# Arduino_Leonardo-REV3b.net
KiCad netlist of a schematic drawn in EAGLE
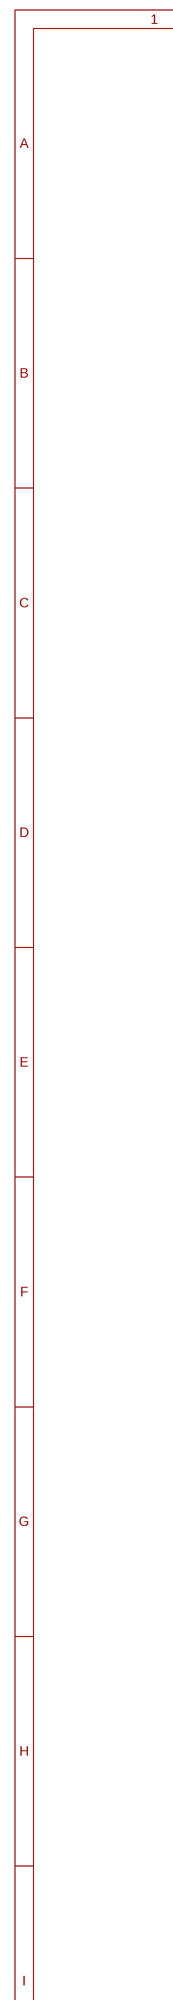
[diagram p0: schematic, sheet 1, part 1 of 2]
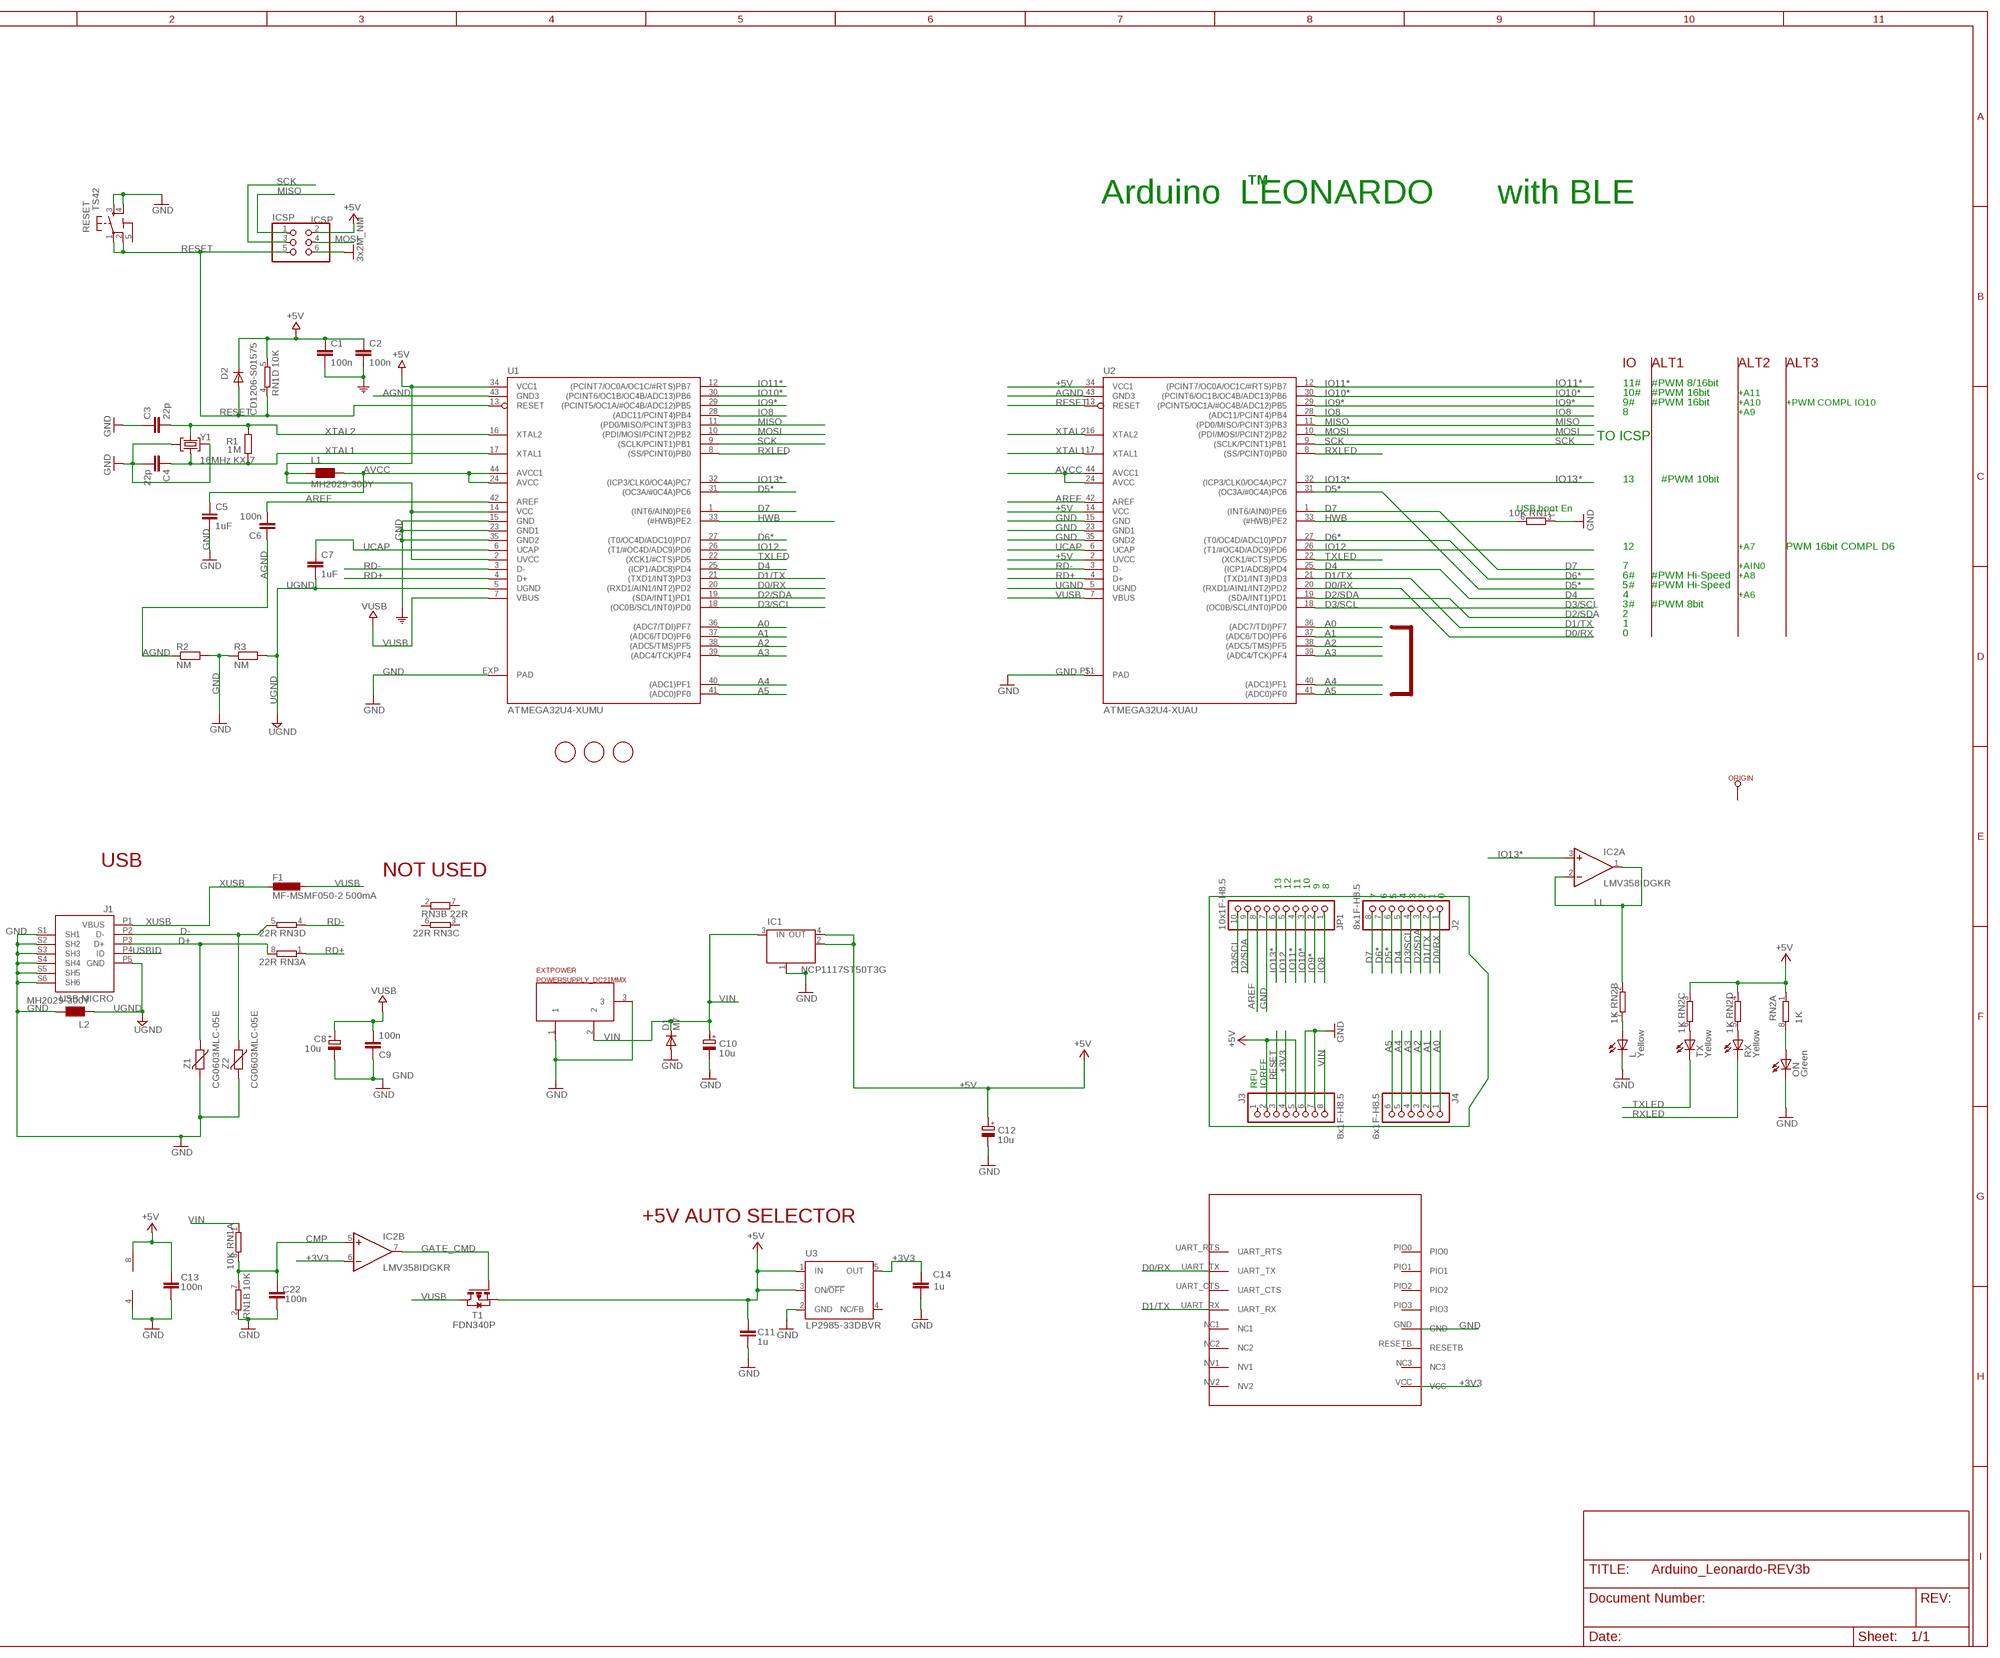
[diagram p1: schematic, sheet 1, part 2 of 2]

(export (version "E")
  (design (tool "Eeschema 10.0.6"))
  (components
    (comp (ref "C1")
      (value "100n")
      (footprint "eagle-import:C0603-ROUND")
      (libsource (lib "eagle-import") (part "C-EUC0603"))
    )
    (comp (ref "C2")
      (value "100n")
      (footprint "eagle-import:C0603-ROUND")
      (libsource (lib "eagle-import") (part "C-EUC0603"))
    )
    (comp (ref "C3")
      (value "22p")
      (footprint "eagle-import:C0603-ROUND")
      (libsource (lib "eagle-import") (part "C-EUC0603"))
    )
    (comp (ref "C4")
      (value "22p")
      (footprint "eagle-import:C0603-ROUND")
      (libsource (lib "eagle-import") (part "C-EUC0603"))
    )
    (comp (ref "C5")
      (value "1uF")
      (footprint "eagle-import:C0603-ROUND")
      (libsource (lib "eagle-import") (part "C-EUC0603"))
    )
    (comp (ref "C6")
      (value "100n")
      (footprint "eagle-import:C0603-ROUND")
      (libsource (lib "eagle-import") (part "C-EUC0603"))
    )
    (comp (ref "C7")
      (value "1uF")
      (footprint "eagle-import:C0603-ROUND")
      (libsource (lib "eagle-import") (part "C-EUC0603"))
    )
    (comp (ref "C8")
      (value "10u")
      (footprint "eagle-import:SMC_B")
      (libsource (lib "eagle-import") (part "CPOL-EUSMCB"))
    )
    (comp (ref "C9")
      (value "100n")
      (footprint "eagle-import:C0603-ROUND")
      (libsource (lib "eagle-import") (part "C-EUC0603"))
    )
    (comp (ref "C10")
      (value "10u")
      (footprint "eagle-import:SMC_B")
      (libsource (lib "eagle-import") (part "CPOL-EUSMCB"))
    )
    (comp (ref "C11")
      (value "1u")
      (footprint "eagle-import:C0603-ROUND")
      (libsource (lib "eagle-import") (part "C-EUC0603"))
    )
    (comp (ref "C12")
      (value "10u")
      (footprint "eagle-import:SMC_B")
      (libsource (lib "eagle-import") (part "CPOL-EUSMCB"))
    )
    (comp (ref "C13")
      (value "100n")
      (footprint "eagle-import:C0603-ROUND")
      (libsource (lib "eagle-import") (part "C-EUC0603"))
    )
    (comp (ref "C14")
      (value "1u")
      (footprint "eagle-import:C0603-ROUND")
      (libsource (lib "eagle-import") (part "C-EUC0603"))
    )
    (comp (ref "C22")
      (value "100n")
      (footprint "eagle-import:C0603-ROUND")
      (libsource (lib "eagle-import") (part "C-EUC0603"))
    )
    (comp (ref "D1")
      (value "M7")
      (footprint "eagle-import:SMB")
      (libsource (lib "eagle-import") (part "DIODE-SMB"))
    )
    (comp (ref "D2")
      (value "CD1206-S01575")
      (footprint "eagle-import:MINIMELF")
      (libsource (lib "eagle-import") (part "DIODE-MINIMELF"))
    )
    (comp (ref "EXTPOWER")
      (value "POWERSUPPLY_DC21MMX")
      (footprint "eagle-import:POWERSUPPLY_DC-21MM")
      (libsource (lib "eagle-import") (part "POWERSUPPLY_DC21MMX"))
    )
    (comp (ref "F1")
      (value "MF-MSMF050-2 500mA")
      (footprint "eagle-import:L1812")
      (libsource (lib "eagle-import") (part "L-EUL1812"))
    )
    (comp (ref "FID1")
      (value "FIDUCIALMOUNT")
      (footprint "eagle-import:FIDUCIA-MOUNT")
      (libsource (lib "eagle-import") (part "FIDUCIALMOUNT"))
    )
    (comp (ref "FID2")
      (value "FIDUCIALMOUNT")
      (footprint "eagle-import:FIDUCIA-MOUNT")
      (libsource (lib "eagle-import") (part "FIDUCIALMOUNT"))
    )
    (comp (ref "FID3")
      (value "FIDUCIALMOUNT")
      (footprint "eagle-import:FIDUCIA-MOUNT")
      (libsource (lib "eagle-import") (part "FIDUCIALMOUNT"))
    )
    (comp (ref "IC1")
      (value "NCP1117ST50T3G")
      (footprint "eagle-import:SOT223")
      (libsource (lib "eagle-import") (part "MC33269ST-3.3T3"))
    )
    (comp (ref "IC2")
      (value "LMV358IDGKR")
      (footprint "eagle-import:MSOP08")
      (libsource (lib "eagle-import") (part "LMV358?MMX"))
    )
    (comp (ref "ICSP")
      (value "ICSP")
      (footprint "eagle-import:2X03")
      (libsource (lib "eagle-import") (part "PINHD-2X3"))
    )
    (comp (ref "J1")
      (value "USB MICRO")
      (footprint "eagle-import:CON2_USB_MICRO_B_AT")
      (libsource (lib "eagle-import") (part "MYCON2_USB-MINI-B"))
    )
    (comp (ref "J2")
      (value "8x1F-H8.5")
      (footprint "eagle-import:1X08")
      (libsource (lib "eagle-import") (part "PINHD-1X8"))
    )
    (comp (ref "J3")
      (value "8x1F-H8.5")
      (footprint "eagle-import:1X08")
      (libsource (lib "eagle-import") (part "PINHD-1X8"))
    )
    (comp (ref "J4")
      (value "6x1F-H8.5")
      (footprint "eagle-import:1X06")
      (libsource (lib "eagle-import") (part "PINHD-1X6"))
    )
    (comp (ref "JP1")
      (value "10x1F-H8.5")
      (footprint "eagle-import:1X10")
      (libsource (lib "eagle-import") (part "PINHD-1X10"))
    )
    (comp (ref "L")
      (value "Yellow")
      (footprint "eagle-import:CHIPLED_0805")
      (libsource (lib "eagle-import") (part "LEDCHIPLED_0805"))
    )
    (comp (ref "L1")
      (value "MH2029-300Y")
      (footprint "eagle-import:0805")
      (libsource (lib "eagle-import") (part "WE-CBF_0805"))
    )
    (comp (ref "L2")
      (value "MH2029-300Y")
      (footprint "eagle-import:0805")
      (libsource (lib "eagle-import") (part "WE-CBF_0805"))
    )
    (comp (ref "ON")
      (value "Green")
      (footprint "eagle-import:CHIPLED_0805")
      (libsource (lib "eagle-import") (part "LEDCHIPLED_0805"))
    )
    (comp (ref "ORIGIN")
      (value "TP_SP")
      (footprint "eagle-import:TP-SP")
      (libsource (lib "eagle-import") (part "TP_SP"))
    )
    (comp (ref "R1")
      (value "1M")
      (footprint "eagle-import:R0603-ROUND")
      (libsource (lib "eagle-import") (part "R-EU_R0603"))
    )
    (comp (ref "R2")
      (value "NM")
      (footprint "eagle-import:R0402")
      (libsource (lib "eagle-import") (part "R-EU_R0402"))
    )
    (comp (ref "R3")
      (value "NM")
      (footprint "eagle-import:R0402")
      (libsource (lib "eagle-import") (part "R-EU_R0402"))
    )
    (comp (ref "RESET")
      (value "TS42")
      (footprint "eagle-import:TS42")
      (libsource (lib "eagle-import") (part "TS42"))
    )
    (comp (ref "RN1")
      (value "10K")
      (footprint "eagle-import:CAY16")
      (libsource (lib "eagle-import") (part "4R-NCAY16"))
    )
    (comp (ref "RN2")
      (value "1K")
      (footprint "eagle-import:CAY16")
      (libsource (lib "eagle-import") (part "4R-NCAY16"))
    )
    (comp (ref "RN3")
      (value "22R")
      (footprint "eagle-import:CAY16")
      (libsource (lib "eagle-import") (part "4R-NCAY16"))
    )
    (comp (ref "RX")
      (value "Yellow")
      (footprint "eagle-import:CHIPLED_0805")
      (libsource (lib "eagle-import") (part "LEDCHIPLED_0805"))
    )
    (comp (ref "T1")
      (value "FDN340P")
      (footprint "eagle-import:SOT-23")
      (libsource (lib "eagle-import") (part "PMOSSOT23"))
    )
    (comp (ref "TX")
      (value "Yellow")
      (footprint "eagle-import:CHIPLED_0805")
      (libsource (lib "eagle-import") (part "LEDCHIPLED_0805"))
    )
    (comp (ref "U$1")
      (value "HM-11")
      (footprint "eagle-import:HM-11")
      (libsource (lib "eagle-import") (part "HM-11"))
    )
    (comp (ref "U1")
      (value "ATMEGA32U4-XUMU")
      (footprint "eagle-import:QFN44ML7X7")
      (libsource (lib "eagle-import") (part "ATMEGA32U4-XUMU"))
    )
    (comp (ref "U2")
      (value "ATMEGA32U4-XUAU")
      (footprint "eagle-import:TQFP44-PAD")
      (libsource (lib "eagle-import") (part "ATMEGA32U4-XUAU"))
    )
    (comp (ref "U3")
      (value "LP2985-33DBVR")
      (footprint "eagle-import:SOT23-DBV")
      (libsource (lib "eagle-import") (part "LP2985-XXDBVR33"))
    )
    (comp (ref "Y1")
      (value "16MHz KX-7")
      (footprint "eagle-import:CRYSTAL-3.2-2.5")
      (libsource (lib "eagle-import") (part "CRYSTAL-3.2-2.5"))
    )
    (comp (ref "Z1")
      (value "CG0603MLC-05E")
      (footprint "eagle-import:CT_CN0603")
      (libsource (lib "eagle-import") (part "VARISTORCN0603"))
    )
    (comp (ref "Z2")
      (value "CG0603MLC-05E")
      (footprint "eagle-import:CT_CN0603")
      (libsource (lib "eagle-import") (part "VARISTORCN0603"))
    )
  )
  (nets
    (net (code "1") (name "+5V") (class "Default")
      (node (ref "C1") (pin "1") (pinfunction "1_1") (pintype "passive"))
      (node (ref "C11") (pin "2") (pinfunction "2_2") (pintype "passive"))
      (node (ref "C12") (pin "+") (pinfunction "+_+") (pintype "passive"))
      (node (ref "C13") (pin "1") (pinfunction "1_1") (pintype "passive"))
      (node (ref "C2") (pin "1") (pinfunction "1_1") (pintype "passive"))
      (node (ref "D2") (pin "C") (pinfunction "C_C") (pintype "passive"))
      (node (ref "IC1") (pin "2") (pinfunction "OUT_2") (pintype "passive"))
      (node (ref "IC1") (pin "4") (pinfunction "OUT_4") (pintype "passive"))
      (node (ref "IC2") (pin "8") (pinfunction "V+_8") (pintype "power_in"))
      (node (ref "ICSP") (pin "2") (pinfunction "2_2") (pintype "passive"))
      (node (ref "J3") (pin "2") (pinfunction "2_2") (pintype "passive"))
      (node (ref "J3") (pin "5") (pinfunction "5_5") (pintype "passive"))
      (node (ref "L1") (pin "1") (pinfunction "1_1") (pintype "passive"))
      (node (ref "RN1") (pin "5") (pinfunction "2_5") (pintype "passive"))
      (node (ref "RN2") (pin "1") (pinfunction "1_1") (pintype "passive"))
      (node (ref "RN2") (pin "3") (pinfunction "1_3") (pintype "passive"))
      (node (ref "RN2") (pin "4") (pinfunction "1_4") (pintype "passive"))
      (node (ref "T1") (pin "2") (pinfunction "S_2") (pintype "passive"))
      (node (ref "U1") (pin "14") (pinfunction "VCC_14") (pintype "power_in"))
      (node (ref "U1") (pin "2") (pinfunction "UVCC_2") (pintype "power_in"))
      (node (ref "U1") (pin "34") (pinfunction "VCC1_34") (pintype "power_in"))
      (node (ref "U2") (pin "14") (pinfunction "VCC_14") (pintype "power_in"))
      (node (ref "U2") (pin "2") (pinfunction "UVCC_2") (pintype "power_in"))
      (node (ref "U2") (pin "34") (pinfunction "VCC1_34") (pintype "power_in"))
      (node (ref "U3") (pin "1") (pinfunction "IN_1") (pintype "input"))
      (node (ref "U3") (pin "3") (pinfunction "ON/~{OFF}_3") (pintype "input"))
    )
    (net (code "2") (name "/+3V3") (class "Default")
      (node (ref "C14") (pin "2") (pinfunction "2_2") (pintype "passive"))
      (node (ref "IC2") (pin "6") (pinfunction "-IN_6") (pintype "input"))
      (node (ref "J3") (pin "4") (pinfunction "4_4") (pintype "passive"))
      (node (ref "U3") (pin "5") (pinfunction "OUT_5") (pintype "passive"))
    )
    (net (code "3") (name "/5-GND") (class "Default")
      (node (ref "RESET") (pin "5") (pinfunction "5-GND_5") (pintype "power_in"))
    )
    (net (code "4") (name "/A0") (class "Default")
      (node (ref "J4") (pin "1") (pinfunction "1_1") (pintype "passive"))
      (node (ref "U1") (pin "36") (pinfunction "(ADC7/TDI)PF7_36") (pintype "bidirectional"))
      (node (ref "U2") (pin "36") (pinfunction "(ADC7/TDI)PF7_36") (pintype "bidirectional"))
    )
    (net (code "5") (name "/A1") (class "Default")
      (node (ref "J4") (pin "2") (pinfunction "2_2") (pintype "passive"))
      (node (ref "U1") (pin "37") (pinfunction "(ADC6/TDO)PF6_37") (pintype "bidirectional"))
      (node (ref "U2") (pin "37") (pinfunction "(ADC6/TDO)PF6_37") (pintype "bidirectional"))
    )
    (net (code "6") (name "/A2") (class "Default")
      (node (ref "J4") (pin "3") (pinfunction "3_3") (pintype "passive"))
      (node (ref "U1") (pin "38") (pinfunction "(ADC5/TMS)PF5_38") (pintype "bidirectional"))
      (node (ref "U2") (pin "38") (pinfunction "(ADC5/TMS)PF5_38") (pintype "bidirectional"))
    )
    (net (code "7") (name "/A3") (class "Default")
      (node (ref "J4") (pin "4") (pinfunction "4_4") (pintype "passive"))
      (node (ref "U1") (pin "39") (pinfunction "(ADC4/TCK)PF4_39") (pintype "bidirectional"))
      (node (ref "U2") (pin "39") (pinfunction "(ADC4/TCK)PF4_39") (pintype "bidirectional"))
    )
    (net (code "8") (name "/A4") (class "Default")
      (node (ref "J4") (pin "5") (pinfunction "5_5") (pintype "passive"))
      (node (ref "U1") (pin "40") (pinfunction "(ADC1)PF1_40") (pintype "bidirectional"))
      (node (ref "U2") (pin "40") (pinfunction "(ADC1)PF1_40") (pintype "bidirectional"))
    )
    (net (code "9") (name "/A5") (class "Default")
      (node (ref "J4") (pin "6") (pinfunction "6_6") (pintype "passive"))
      (node (ref "U1") (pin "41") (pinfunction "(ADC0)PF0_41") (pintype "bidirectional"))
      (node (ref "U2") (pin "41") (pinfunction "(ADC0)PF0_41") (pintype "bidirectional"))
    )
    (net (code "10") (name "/AGND") (class "Default")
      (node (ref "C6") (pin "1") (pinfunction "1_1") (pintype "passive"))
      (node (ref "R2") (pin "1") (pinfunction "1_1") (pintype "passive"))
      (node (ref "U1") (pin "43") (pinfunction "GND3_43") (pintype "power_in"))
      (node (ref "U2") (pin "43") (pinfunction "GND3_43") (pintype "power_in"))
    )
    (net (code "11") (name "/AREF") (class "Default")
      (node (ref "C6") (pin "2") (pinfunction "2_2") (pintype "passive"))
      (node (ref "JP1") (pin "8") (pinfunction "8_8") (pintype "passive"))
      (node (ref "U1") (pin "42") (pinfunction "AREF_42") (pintype "power_in"))
      (node (ref "U2") (pin "42") (pinfunction "AREF_42") (pintype "power_in"))
    )
    (net (code "12") (name "/AVCC") (class "Default")
      (node (ref "C5") (pin "1") (pinfunction "1_1") (pintype "passive"))
      (node (ref "L1") (pin "2") (pinfunction "2_2") (pintype "passive"))
      (node (ref "U1") (pin "24") (pinfunction "AVCC_24") (pintype "power_in"))
      (node (ref "U1") (pin "44") (pinfunction "AVCC1_44") (pintype "power_in"))
      (node (ref "U2") (pin "24") (pinfunction "AVCC_24") (pintype "power_in"))
      (node (ref "U2") (pin "44") (pinfunction "AVCC1_44") (pintype "power_in"))
    )
    (net (code "13") (name "/CMP") (class "Default")
      (node (ref "C22") (pin "2") (pinfunction "2_2") (pintype "passive"))
      (node (ref "IC2") (pin "5") (pinfunction "+IN_5") (pintype "input"))
      (node (ref "RN1") (pin "7") (pinfunction "2_7") (pintype "passive"))
      (node (ref "RN1") (pin "8") (pinfunction "2_8") (pintype "passive"))
    )
    (net (code "14") (name "/D+") (class "Default")
      (node (ref "J1") (pin "P3") (pinfunction "D+_P3") (pintype "bidirectional"))
      (node (ref "RN3") (pin "8") (pinfunction "2_8") (pintype "passive"))
      (node (ref "Z1") (pin "1") (pinfunction "1_1") (pintype "passive"))
    )
    (net (code "15") (name "/D-") (class "Default")
      (node (ref "J1") (pin "P2") (pinfunction "D-_P2") (pintype "bidirectional"))
      (node (ref "RN3") (pin "5") (pinfunction "2_5") (pintype "passive"))
      (node (ref "Z2") (pin "1") (pinfunction "1_1") (pintype "passive"))
    )
    (net (code "16") (name "/D0{slash}RX") (class "Default")
      (node (ref "J2") (pin "1") (pinfunction "1_1") (pintype "passive"))
      (node (ref "U$1") (pin "UART_TX") (pinfunction "UART_TX_UART_TX") (pintype "bidirectional"))
      (node (ref "U1") (pin "20") (pinfunction "(RXD1/AIN1/INT2)PD2_20") (pintype "bidirectional"))
      (node (ref "U2") (pin "20") (pinfunction "(RXD1/AIN1/INT2)PD2_20") (pintype "bidirectional"))
    )
    (net (code "17") (name "/D1{slash}TX") (class "Default")
      (node (ref "J2") (pin "2") (pinfunction "2_2") (pintype "passive"))
      (node (ref "U$1") (pin "UART_RX") (pinfunction "UART_RX_UART_RX") (pintype "bidirectional"))
      (node (ref "U1") (pin "21") (pinfunction "(TXD1/INT3)PD3_21") (pintype "bidirectional"))
      (node (ref "U2") (pin "21") (pinfunction "(TXD1/INT3)PD3_21") (pintype "bidirectional"))
    )
    (net (code "18") (name "/D2{slash}SDA") (class "Default")
      (node (ref "J2") (pin "3") (pinfunction "3_3") (pintype "passive"))
      (node (ref "JP1") (pin "9") (pinfunction "9_9") (pintype "passive"))
      (node (ref "U1") (pin "19") (pinfunction "(SDA/INT1)PD1_19") (pintype "bidirectional"))
      (node (ref "U2") (pin "19") (pinfunction "(SDA/INT1)PD1_19") (pintype "bidirectional"))
    )
    (net (code "19") (name "/D3{slash}SCL") (class "Default")
      (node (ref "J2") (pin "4") (pinfunction "4_4") (pintype "passive"))
      (node (ref "JP1") (pin "10") (pinfunction "10_10") (pintype "passive"))
      (node (ref "U1") (pin "18") (pinfunction "(OC0B/SCL/INT0)PD0_18") (pintype "bidirectional"))
      (node (ref "U2") (pin "18") (pinfunction "(OC0B/SCL/INT0)PD0_18") (pintype "bidirectional"))
    )
    (net (code "20") (name "/D4") (class "Default")
      (node (ref "J2") (pin "5") (pinfunction "5_5") (pintype "passive"))
      (node (ref "U1") (pin "25") (pinfunction "(ICP1/ADC8)PD4_25") (pintype "bidirectional"))
      (node (ref "U2") (pin "25") (pinfunction "(ICP1/ADC8)PD4_25") (pintype "bidirectional"))
    )
    (net (code "21") (name "/D5*") (class "Default")
      (node (ref "J2") (pin "6") (pinfunction "6_6") (pintype "passive"))
      (node (ref "U1") (pin "31") (pinfunction "(OC3A/#0C4A)PC6_31") (pintype "bidirectional"))
      (node (ref "U2") (pin "31") (pinfunction "(OC3A/#0C4A)PC6_31") (pintype "bidirectional"))
    )
    (net (code "22") (name "/D6*") (class "Default")
      (node (ref "J2") (pin "7") (pinfunction "7_7") (pintype "passive"))
      (node (ref "U1") (pin "27") (pinfunction "(T0/OC4D/ADC10)PD7_27") (pintype "bidirectional"))
      (node (ref "U2") (pin "27") (pinfunction "(T0/OC4D/ADC10)PD7_27") (pintype "bidirectional"))
    )
    (net (code "23") (name "/D7") (class "Default")
      (node (ref "J2") (pin "8") (pinfunction "8_8") (pintype "passive"))
      (node (ref "U1") (pin "1") (pinfunction "(INT6/AIN0)PE6_1") (pintype "bidirectional"))
      (node (ref "U2") (pin "1") (pinfunction "(INT6/AIN0)PE6_1") (pintype "bidirectional"))
    )
    (net (code "24") (name "/GATE_CMD") (class "Default")
      (node (ref "IC2") (pin "7") (pinfunction "OUT_7") (pintype "output"))
      (node (ref "T1") (pin "3") (pinfunction "G_3") (pintype "passive"))
    )
    (net (code "25") (name "/HWB") (class "Default")
      (node (ref "RN1") (pin "6") (pinfunction "2_6") (pintype "passive"))
      (node (ref "U1") (pin "33") (pinfunction "(#HWB)PE2_33") (pintype "bidirectional"))
      (node (ref "U2") (pin "33") (pinfunction "(#HWB)PE2_33") (pintype "bidirectional"))
    )
    (net (code "26") (name "/IO8") (class "Default")
      (node (ref "JP1") (pin "1") (pinfunction "1_1") (pintype "passive"))
      (node (ref "U1") (pin "28") (pinfunction "(ADC11/PCINT4)PB4_28") (pintype "bidirectional"))
      (node (ref "U2") (pin "28") (pinfunction "(ADC11/PCINT4)PB4_28") (pintype "bidirectional"))
    )
    (net (code "27") (name "/IO9*") (class "Default")
      (node (ref "JP1") (pin "2") (pinfunction "2_2") (pintype "passive"))
      (node (ref "U1") (pin "29") (pinfunction "(PCINT5/OC1A/#OC4B/ADC12)PB5_29") (pintype "bidirectional"))
      (node (ref "U2") (pin "29") (pinfunction "(PCINT5/OC1A/#OC4B/ADC12)PB5_29") (pintype "bidirectional"))
    )
    (net (code "28") (name "/IO10*") (class "Default")
      (node (ref "JP1") (pin "3") (pinfunction "3_3") (pintype "passive"))
      (node (ref "U1") (pin "30") (pinfunction "(PCINT6/OC1B/OC4B/ADC13)PB6_30") (pintype "bidirectional"))
      (node (ref "U2") (pin "30") (pinfunction "(PCINT6/OC1B/OC4B/ADC13)PB6_30") (pintype "bidirectional"))
    )
    (net (code "29") (name "/IO11*") (class "Default")
      (node (ref "JP1") (pin "4") (pinfunction "4_4") (pintype "passive"))
      (node (ref "U1") (pin "12") (pinfunction "(PCINT7/OC0A/OC1C/#RTS)PB7_12") (pintype "bidirectional"))
      (node (ref "U2") (pin "12") (pinfunction "(PCINT7/OC0A/OC1C/#RTS)PB7_12") (pintype "bidirectional"))
    )
    (net (code "30") (name "/IO12") (class "Default")
      (node (ref "JP1") (pin "5") (pinfunction "5_5") (pintype "passive"))
      (node (ref "U1") (pin "26") (pinfunction "(T1/#OC4D/ADC9)PD6_26") (pintype "bidirectional"))
      (node (ref "U2") (pin "26") (pinfunction "(T1/#OC4D/ADC9)PD6_26") (pintype "bidirectional"))
    )
    (net (code "31") (name "/IO13*") (class "Default")
      (node (ref "IC2") (pin "3") (pinfunction "+IN_3") (pintype "input"))
      (node (ref "JP1") (pin "6") (pinfunction "6_6") (pintype "passive"))
      (node (ref "U1") (pin "32") (pinfunction "(ICP3/CLK0/OC4A)PC7_32") (pintype "bidirectional"))
      (node (ref "U2") (pin "32") (pinfunction "(ICP3/CLK0/OC4A)PC7_32") (pintype "bidirectional"))
    )
    (net (code "32") (name "/LL") (class "Default")
      (node (ref "IC2") (pin "1") (pinfunction "OUT_1") (pintype "output"))
      (node (ref "IC2") (pin "2") (pinfunction "-IN_2") (pintype "input"))
      (node (ref "RN2") (pin "2") (pinfunction "1_2") (pintype "passive"))
    )
    (net (code "33") (name "/MISO") (class "Default")
      (node (ref "ICSP") (pin "1") (pinfunction "1_1") (pintype "passive"))
      (node (ref "U1") (pin "11") (pinfunction "(PD0/MISO/PCINT3)PB3_11") (pintype "bidirectional"))
      (node (ref "U2") (pin "11") (pinfunction "(PD0/MISO/PCINT3)PB3_11") (pintype "bidirectional"))
    )
    (net (code "34") (name "/MOSI") (class "Default")
      (node (ref "ICSP") (pin "4") (pinfunction "4_4") (pintype "passive"))
      (node (ref "U1") (pin "10") (pinfunction "(PDI/MOSI/PCINT2)PB2_10") (pintype "bidirectional"))
      (node (ref "U2") (pin "10") (pinfunction "(PDI/MOSI/PCINT2)PB2_10") (pintype "bidirectional"))
    )
    (net (code "35") (name "/RD+") (class "Default")
      (node (ref "RN3") (pin "1") (pinfunction "1_1") (pintype "passive"))
      (node (ref "U1") (pin "4") (pinfunction "D+_4") (pintype "bidirectional"))
      (node (ref "U2") (pin "4") (pinfunction "D+_4") (pintype "bidirectional"))
    )
    (net (code "36") (name "/RD-") (class "Default")
      (node (ref "RN3") (pin "4") (pinfunction "1_4") (pintype "passive"))
      (node (ref "U1") (pin "3") (pinfunction "D-_3") (pintype "bidirectional"))
      (node (ref "U2") (pin "3") (pinfunction "D-_3") (pintype "bidirectional"))
    )
    (net (code "37") (name "/RESET") (class "Default")
      (node (ref "D2") (pin "A") (pinfunction "A_A") (pintype "passive"))
      (node (ref "ICSP") (pin "5") (pinfunction "5_5") (pintype "passive"))
      (node (ref "J3") (pin "3") (pinfunction "3_3") (pintype "passive"))
      (node (ref "RESET") (pin "1") (pinfunction "1_1") (pintype "passive"))
      (node (ref "RESET") (pin "2") (pinfunction "2_2") (pintype "passive"))
      (node (ref "RN1") (pin "4") (pinfunction "1_4") (pintype "passive"))
      (node (ref "U1") (pin "13") (pinfunction "RESET_13") (pintype "input"))
      (node (ref "U2") (pin "13") (pinfunction "RESET_13") (pintype "input"))
    )
    (net (code "38") (name "/RXLED") (class "Default")
      (node (ref "RX") (pin "C") (pinfunction "C_C") (pintype "passive"))
      (node (ref "U1") (pin "8") (pinfunction "(SS/PCINT0)PB0_8") (pintype "bidirectional"))
      (node (ref "U2") (pin "8") (pinfunction "(SS/PCINT0)PB0_8") (pintype "bidirectional"))
    )
    (net (code "39") (name "/SCK") (class "Default")
      (node (ref "ICSP") (pin "3") (pinfunction "3_3") (pintype "passive"))
      (node (ref "U1") (pin "9") (pinfunction "(SCLK/PCINT1)PB1_9") (pintype "bidirectional"))
      (node (ref "U2") (pin "9") (pinfunction "(SCLK/PCINT1)PB1_9") (pintype "bidirectional"))
    )
    (net (code "40") (name "/TXLED") (class "Default")
      (node (ref "TX") (pin "C") (pinfunction "C_C") (pintype "passive"))
      (node (ref "U1") (pin "22") (pinfunction "(XCK1/#CTS)PD5_22") (pintype "bidirectional"))
      (node (ref "U2") (pin "22") (pinfunction "(XCK1/#CTS)PD5_22") (pintype "bidirectional"))
    )
    (net (code "41") (name "/UCAP") (class "Default")
      (node (ref "C7") (pin "1") (pinfunction "1_1") (pintype "passive"))
      (node (ref "U1") (pin "6") (pinfunction "UCAP_6") (pintype "passive"))
      (node (ref "U2") (pin "6") (pinfunction "UCAP_6") (pintype "passive"))
    )
    (net (code "42") (name "/USBID") (class "Default")
      (node (ref "J1") (pin "P4") (pinfunction "ID_P4") (pintype "bidirectional"))
    )
    (net (code "43") (name "/VIN") (class "Default")
      (node (ref "C10") (pin "+") (pinfunction "+_+") (pintype "passive"))
      (node (ref "D1") (pin "C") (pinfunction "C_C") (pintype "passive"))
      (node (ref "EXTPOWER") (pin "2") (pinfunction "2_2") (pintype "power_in"))
      (node (ref "IC1") (pin "3") (pinfunction "IN_3") (pintype "input"))
      (node (ref "J3") (pin "8") (pinfunction "8_8") (pintype "passive"))
      (node (ref "RN1") (pin "1") (pinfunction "1_1") (pintype "passive"))
    )
    (net (code "44") (name "/XTAL1") (class "Default")
      (node (ref "C4") (pin "1") (pinfunction "1_1") (pintype "passive"))
      (node (ref "R1") (pin "1") (pinfunction "1_1") (pintype "passive"))
      (node (ref "U1") (pin "17") (pinfunction "XTAL1_17") (pintype "bidirectional"))
      (node (ref "U2") (pin "17") (pinfunction "XTAL1_17") (pintype "bidirectional"))
      (node (ref "Y1") (pin "1") (pinfunction "C1_1") (pintype "passive"))
    )
    (net (code "45") (name "/XTAL2") (class "Default")
      (node (ref "C3") (pin "2") (pinfunction "2_2") (pintype "passive"))
      (node (ref "R1") (pin "2") (pinfunction "2_2") (pintype "passive"))
      (node (ref "U1") (pin "16") (pinfunction "XTAL2_16") (pintype "bidirectional"))
      (node (ref "U2") (pin "16") (pinfunction "XTAL2_16") (pintype "bidirectional"))
      (node (ref "Y1") (pin "3") (pinfunction "C2_3") (pintype "passive"))
    )
    (net (code "46") (name "/XUSB") (class "Default")
      (node (ref "F1") (pin "2") (pinfunction "2_2") (pintype "passive"))
      (node (ref "J1") (pin "P1") (pinfunction "VBUS_P1") (pintype "power_in"))
    )
    (net (code "47") (name "3x2M_NM") (class "Default")
      (node (ref "C1") (pin "2") (pinfunction "2_2") (pintype "passive"))
      (node (ref "C10") (pin "-") (pinfunction "-_-") (pintype "passive"))
      (node (ref "C11") (pin "1") (pinfunction "1_1") (pintype "passive"))
      (node (ref "C12") (pin "-") (pinfunction "-_-") (pintype "passive"))
      (node (ref "C13") (pin "2") (pinfunction "2_2") (pintype "passive"))
      (node (ref "C14") (pin "1") (pinfunction "1_1") (pintype "passive"))
      (node (ref "C2") (pin "2") (pinfunction "2_2") (pintype "passive"))
      (node (ref "C22") (pin "1") (pinfunction "1_1") (pintype "passive"))
      (node (ref "C3") (pin "1") (pinfunction "1_1") (pintype "passive"))
      (node (ref "C4") (pin "2") (pinfunction "2_2") (pintype "passive"))
      (node (ref "C5") (pin "2") (pinfunction "2_2") (pintype "passive"))
      (node (ref "C8") (pin "-") (pinfunction "-_-") (pintype "passive"))
      (node (ref "C9") (pin "1") (pinfunction "1_1") (pintype "passive"))
      (node (ref "D1") (pin "A") (pinfunction "A_A") (pintype "passive"))
      (node (ref "EXTPOWER") (pin "1") (pinfunction "1_1") (pintype "power_in"))
      (node (ref "EXTPOWER") (pin "3") (pinfunction "3_3") (pintype "power_in"))
      (node (ref "IC1") (pin "1") (pinfunction "GND/ADJ_1") (pintype "input"))
      (node (ref "IC2") (pin "4") (pinfunction "V-_4") (pintype "power_in"))
      (node (ref "ICSP") (pin "6") (pinfunction "6_6") (pintype "passive"))
      (node (ref "J1") (pin "S1") (pinfunction "SH1_S1") (pintype "passive"))
      (node (ref "J1") (pin "S2") (pinfunction "SH2_S2") (pintype "passive"))
      (node (ref "J1") (pin "S3") (pinfunction "SH3_S3") (pintype "passive"))
      (node (ref "J1") (pin "S4") (pinfunction "SH4_S4") (pintype "passive"))
      (node (ref "J1") (pin "S5") (pinfunction "SH5_S5") (pintype "passive"))
      (node (ref "J1") (pin "S6") (pinfunction "SH6_S6") (pintype "passive"))
      (node (ref "J3") (pin "6") (pinfunction "6_6") (pintype "passive"))
      (node (ref "J3") (pin "7") (pinfunction "7_7") (pintype "passive"))
      (node (ref "JP1") (pin "7") (pinfunction "7_7") (pintype "passive"))
      (node (ref "L") (pin "C") (pinfunction "C_C") (pintype "passive"))
      (node (ref "L2") (pin "2") (pinfunction "2_2") (pintype "passive"))
      (node (ref "ON") (pin "C") (pinfunction "C_C") (pintype "passive"))
      (node (ref "R2") (pin "2") (pinfunction "2_2") (pintype "passive"))
      (node (ref "R3") (pin "1") (pinfunction "1_1") (pintype "passive"))
      (node (ref "RESET") (pin "3") (pinfunction "3_3") (pintype "passive"))
      (node (ref "RESET") (pin "4") (pinfunction "4_4") (pintype "passive"))
      (node (ref "RN1") (pin "2") (pinfunction "1_2") (pintype "passive"))
      (node (ref "RN1") (pin "3") (pinfunction "1_3") (pintype "passive"))
      (node (ref "U1") (pin "15") (pinfunction "GND_15") (pintype "power_in"))
      (node (ref "U1") (pin "23") (pinfunction "GND1_23") (pintype "power_in"))
      (node (ref "U1") (pin "35") (pinfunction "GND2_35") (pintype "power_in"))
      (node (ref "U1") (pin "EXP") (pinfunction "PAD_EXP") (pintype "power_in"))
      (node (ref "U2") (pin "15") (pinfunction "GND_15") (pintype "power_in"))
      (node (ref "U2") (pin "23") (pinfunction "GND1_23") (pintype "power_in"))
      (node (ref "U2") (pin "35") (pinfunction "GND2_35") (pintype "power_in"))
      (node (ref "U2") (pin "P$1") (pinfunction "PAD_P$1") (pintype "power_in"))
      (node (ref "U3") (pin "2") (pinfunction "GND_2") (pintype "power_in"))
      (node (ref "Y1") (pin "2") (pinfunction "GND_2") (pintype "passive"))
      (node (ref "Y1") (pin "4") (pinfunction "GND_4") (pintype "passive"))
      (node (ref "Z1") (pin "2") (pinfunction "2_2") (pintype "passive"))
      (node (ref "Z2") (pin "2") (pinfunction "2_2") (pintype "passive"))
    )
    (net (code "48") (name "Net-(RN2A-2)") (class "Default")
      (node (ref "ON") (pin "A") (pinfunction "A_A") (pintype "passive"))
      (node (ref "RN2") (pin "8") (pinfunction "2_8") (pintype "passive"))
    )
    (net (code "49") (name "Net-(RN2B-2)") (class "Default")
      (node (ref "L") (pin "A") (pinfunction "A_A") (pintype "passive"))
      (node (ref "RN2") (pin "7") (pinfunction "2_7") (pintype "passive"))
    )
    (net (code "50") (name "Net-(RN2C-2)") (class "Default")
      (node (ref "RN2") (pin "6") (pinfunction "2_6") (pintype "passive"))
      (node (ref "TX") (pin "A") (pinfunction "A_A") (pintype "passive"))
    )
    (net (code "51") (name "Net-(RN2D-2)") (class "Default")
      (node (ref "RN2") (pin "5") (pinfunction "2_5") (pintype "passive"))
      (node (ref "RX") (pin "A") (pinfunction "A_A") (pintype "passive"))
    )
    (net (code "52") (name "UGND") (class "Default")
      (node (ref "C7") (pin "2") (pinfunction "2_2") (pintype "passive"))
      (node (ref "J1") (pin "P5") (pinfunction "GND_P5") (pintype "passive"))
      (node (ref "L2") (pin "1") (pinfunction "1_1") (pintype "passive"))
      (node (ref "R3") (pin "2") (pinfunction "2_2") (pintype "passive"))
      (node (ref "U1") (pin "5") (pinfunction "UGND_5") (pintype "power_in"))
      (node (ref "U2") (pin "5") (pinfunction "UGND_5") (pintype "power_in"))
    )
    (net (code "53") (name "VUSB") (class "Default")
      (node (ref "C8") (pin "+") (pinfunction "+_+") (pintype "passive"))
      (node (ref "C9") (pin "2") (pinfunction "2_2") (pintype "passive"))
      (node (ref "F1") (pin "1") (pinfunction "1_1") (pintype "passive"))
      (node (ref "T1") (pin "1") (pinfunction "D_1") (pintype "passive"))
      (node (ref "U1") (pin "7") (pinfunction "VBUS_7") (pintype "input"))
      (node (ref "U2") (pin "7") (pinfunction "VBUS_7") (pintype "input"))
    )
    (net (code "54") (name "unconnected-(J3-Pad1)") (class "Default")
      (node (ref "J3") (pin "1") (pinfunction "1_1") (pintype "passive"))
    )
    (net (code "55") (name "unconnected-(ORIGIN-TESTP-PadX)") (class "Default")
      (node (ref "ORIGIN") (pin "X") (pinfunction "TESTP_X") (pintype "passive"))
    )
    (net (code "56") (name "unconnected-(RN3B-1-Pad2)") (class "Default")
      (node (ref "RN3") (pin "2") (pinfunction "1_2") (pintype "passive"))
    )
    (net (code "57") (name "unconnected-(RN3B-2-Pad7)") (class "Default")
      (node (ref "RN3") (pin "7") (pinfunction "2_7") (pintype "passive"))
    )
    (net (code "58") (name "unconnected-(RN3C-1-Pad3)") (class "Default")
      (node (ref "RN3") (pin "3") (pinfunction "1_3") (pintype "passive"))
    )
    (net (code "59") (name "unconnected-(RN3C-2-Pad6)") (class "Default")
      (node (ref "RN3") (pin "6") (pinfunction "2_6") (pintype "passive"))
    )
    (net (code "60") (name "unconnected-(U$1-PadGND)") (class "Default")
      (node (ref "U$1") (pin "GND") (pinfunction "GND_GND") (pintype "bidirectional"))
    )
    (net (code "61") (name "unconnected-(U$1-PadNC1)") (class "Default")
      (node (ref "U$1") (pin "NC1") (pinfunction "NC1_NC1") (pintype "bidirectional"))
    )
    (net (code "62") (name "unconnected-(U$1-PadNC2)") (class "Default")
      (node (ref "U$1") (pin "NC2") (pinfunction "NC2_NC2") (pintype "bidirectional"))
    )
    (net (code "63") (name "unconnected-(U$1-PadNC3)") (class "Default")
      (node (ref "U$1") (pin "NC3") (pinfunction "NC3_NC3") (pintype "bidirectional"))
    )
    (net (code "64") (name "unconnected-(U$1-PadNV1)") (class "Default")
      (node (ref "U$1") (pin "NV1") (pinfunction "NV1_NV1") (pintype "bidirectional"))
    )
    (net (code "65") (name "unconnected-(U$1-PadNV2)") (class "Default")
      (node (ref "U$1") (pin "NV2") (pinfunction "NV2_NV2") (pintype "bidirectional"))
    )
    (net (code "66") (name "unconnected-(U$1-PadPIO0)") (class "Default")
      (node (ref "U$1") (pin "PIO0") (pinfunction "PIO0_PIO0") (pintype "bidirectional"))
    )
    (net (code "67") (name "unconnected-(U$1-PadPIO1)") (class "Default")
      (node (ref "U$1") (pin "PIO1") (pinfunction "PIO1_PIO1") (pintype "bidirectional"))
    )
    (net (code "68") (name "unconnected-(U$1-PadPIO2)") (class "Default")
      (node (ref "U$1") (pin "PIO2") (pinfunction "PIO2_PIO2") (pintype "bidirectional"))
    )
    (net (code "69") (name "unconnected-(U$1-PadPIO3)") (class "Default")
      (node (ref "U$1") (pin "PIO3") (pinfunction "PIO3_PIO3") (pintype "bidirectional"))
    )
    (net (code "70") (name "unconnected-(U$1-PadRESETB)") (class "Default")
      (node (ref "U$1") (pin "RESETB") (pinfunction "RESETB_RESETB") (pintype "bidirectional"))
    )
    (net (code "71") (name "unconnected-(U$1-PadUART_CTS)") (class "Default")
      (node (ref "U$1") (pin "UART_CTS") (pinfunction "UART_CTS_UART_CTS") (pintype "bidirectional"))
    )
    (net (code "72") (name "unconnected-(U$1-PadUART_RTS)") (class "Default")
      (node (ref "U$1") (pin "UART_RTS") (pinfunction "UART_RTS_UART_RTS") (pintype "bidirectional"))
    )
    (net (code "73") (name "unconnected-(U$1-PadVCC)") (class "Default")
      (node (ref "U$1") (pin "VCC") (pinfunction "VCC_VCC") (pintype "bidirectional"))
    )
    (net (code "74") (name "unconnected-(U3-NC{slash}FB-Pad4)") (class "Default")
      (node (ref "U3") (pin "4") (pinfunction "NC/FB_4") (pintype "passive"))
    )
  )
)
